# Hot_tub_fill_flow_meter.net
KiCad netlist of a schematic drawn in EAGLE
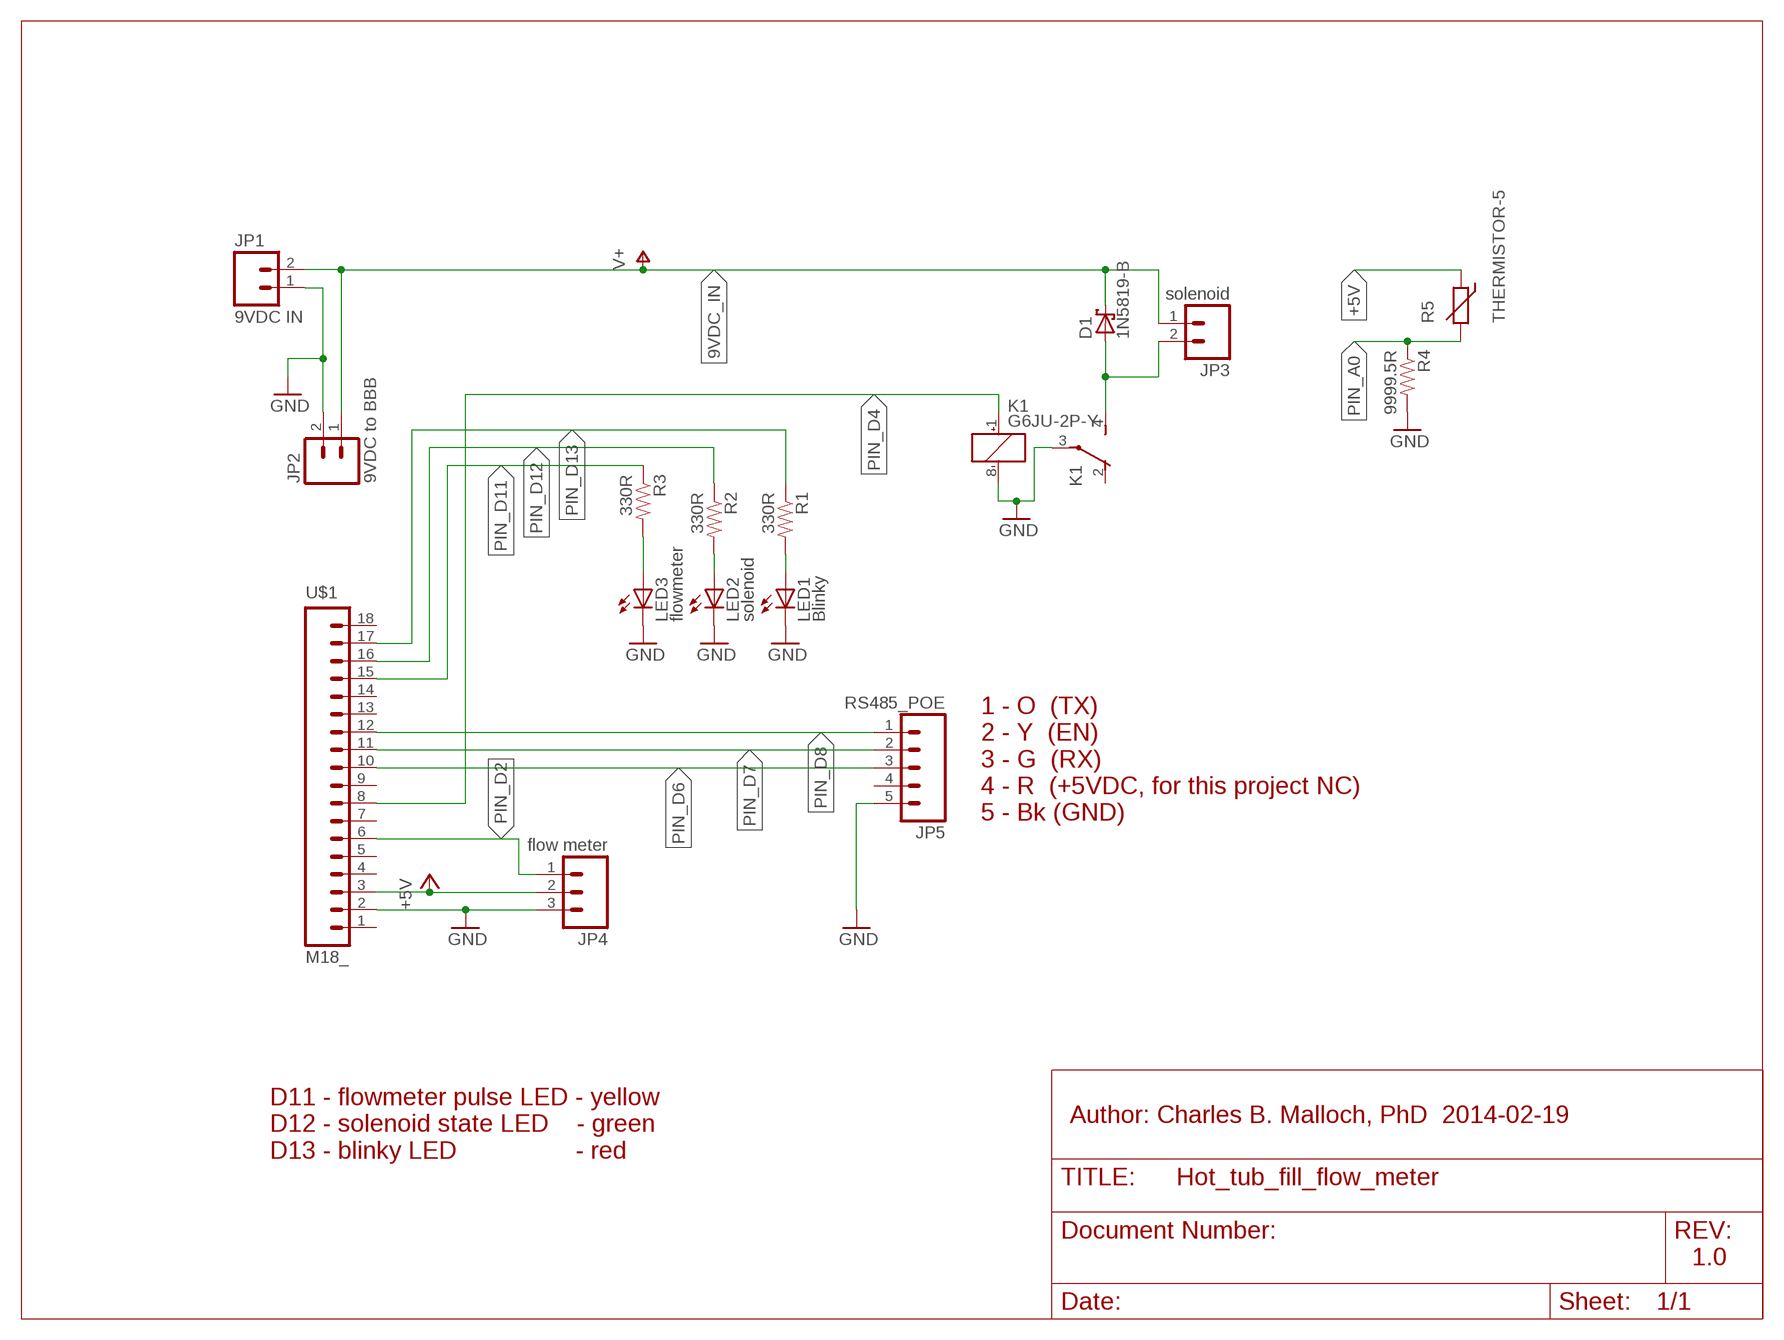
[diagram p0: schematic, sheet 1]

(export (version "E")
  (design (tool "Eeschema 10.0.6"))
  (components
    (comp (ref "D1")
      (value "1N5819-B")
      (footprint "eagle-import:DO41-7.6")
      (libsource (lib "eagle-import") (part "1N5819-B"))
    )
    (comp (ref "JP1")
      (value "9VDC IN")
      (footprint "eagle-import:1X02_LOCK")
      (libsource (lib "eagle-import") (part "M02LOCK"))
    )
    (comp (ref "JP2")
      (value "9VDC to BBB")
      (footprint "eagle-import:1X02_LOCK")
      (libsource (lib "eagle-import") (part "M02LOCK"))
    )
    (comp (ref "JP3")
      (value "solenoid")
      (footprint "eagle-import:1X02_LOCK")
      (libsource (lib "eagle-import") (part "M02LOCK"))
    )
    (comp (ref "JP4")
      (value "flow meter")
      (footprint "eagle-import:1X03_LOCK")
      (libsource (lib "eagle-import") (part "M03LOCK"))
    )
    (comp (ref "JP5")
      (value "RS485_POE")
      (footprint "eagle-import:1X05")
      (libsource (lib "eagle-import") (part "M05PTH"))
    )
    (comp (ref "K1")
      (value "G6JU-2P-Y")
      (footprint "eagle-import:G6J-2P-Y")
      (fields (field (name "MF") "OMRON COMPONENTS USA") (field (name "MPN") "G6JU-2P-Y-DC12"))
      (libsource (lib "eagle-import") (part "G6J-2?-YPU"))
    )
    (comp (ref "LED1")
      (value "Blinky")
      (footprint "eagle-import:LED5MM")
      (libsource (lib "eagle-import") (part "LED5MM"))
    )
    (comp (ref "LED2")
      (value "solenoid")
      (footprint "eagle-import:LED5MM")
      (libsource (lib "eagle-import") (part "LED5MM"))
    )
    (comp (ref "LED3")
      (value "flowmeter")
      (footprint "eagle-import:LED5MM")
      (libsource (lib "eagle-import") (part "LED5MM"))
    )
    (comp (ref "R1")
      (value "330R")
      (footprint "eagle-import:AXIAL-0.3")
      (libsource (lib "eagle-import") (part "RESISTORAXIAL-0.3"))
    )
    (comp (ref "R2")
      (value "330R")
      (footprint "eagle-import:AXIAL-0.3")
      (libsource (lib "eagle-import") (part "RESISTORAXIAL-0.3"))
    )
    (comp (ref "R3")
      (value "330R")
      (footprint "eagle-import:AXIAL-0.3")
      (libsource (lib "eagle-import") (part "RESISTORAXIAL-0.3"))
    )
    (comp (ref "R4")
      (value "9999.5R")
      (footprint "eagle-import:AXIAL-0.3")
      (libsource (lib "eagle-import") (part "RESISTORAXIAL-0.3"))
    )
    (comp (ref "R5")
      (value "THERMISTOR-5")
      (footprint "eagle-import:R-5")
      (libsource (lib "eagle-import") (part "THERMISTOR-5"))
    )
    (comp (ref "U$1")
      (value "M18_")
      (footprint "eagle-import:1X18")
      (libsource (lib "eagle-import") (part "M18_"))
    )
  )
  (nets
    (net (code "1") (name "+5V") (class "Default")
      (node (ref "JP4") (pin "2") (pinfunction "2_2") (pintype "passive"))
      (node (ref "R5") (pin "1") (pinfunction "1_1") (pintype "passive"))
      (node (ref "U$1") (pin "3") (pinfunction "3_3") (pintype "passive"))
    )
    (net (code "2") (name "9VDC_IN") (class "Default")
      (node (ref "D1") (pin "C") (pinfunction "C_C") (pintype "passive"))
      (node (ref "JP1") (pin "2") (pinfunction "2_2") (pintype "passive"))
      (node (ref "JP2") (pin "1") (pinfunction "1_1") (pintype "passive"))
      (node (ref "JP3") (pin "1") (pinfunction "1_1") (pintype "passive"))
    )
    (net (code "3") (name "GND") (class "Default")
      (node (ref "JP1") (pin "1") (pinfunction "1_1") (pintype "passive"))
      (node (ref "JP2") (pin "2") (pinfunction "2_2") (pintype "passive"))
      (node (ref "JP4") (pin "3") (pinfunction "3_3") (pintype "passive"))
      (node (ref "JP5") (pin "5") (pinfunction "5_5") (pintype "passive"))
      (node (ref "K1") (pin "3") (pinfunction "P_3") (pintype "passive"))
      (node (ref "K1") (pin "8") (pinfunction "-_8") (pintype "passive"))
      (node (ref "LED1") (pin "K") (pinfunction "C_K") (pintype "passive"))
      (node (ref "LED2") (pin "K") (pinfunction "C_K") (pintype "passive"))
      (node (ref "LED3") (pin "K") (pinfunction "C_K") (pintype "passive"))
      (node (ref "R4") (pin "P$2") (pinfunction "2_P$2") (pintype "passive"))
      (node (ref "U$1") (pin "2") (pinfunction "2_2") (pintype "passive"))
    )
    (net (code "4") (name "Net-(K1B-S)") (class "Default")
      (node (ref "D1") (pin "A") (pinfunction "A_A") (pintype "passive"))
      (node (ref "JP3") (pin "2") (pinfunction "2_2") (pintype "passive"))
      (node (ref "K1") (pin "4") (pinfunction "S_4") (pintype "passive"))
    )
    (net (code "5") (name "Net-(R1-2)") (class "Default")
      (node (ref "LED1") (pin "A") (pinfunction "A_A") (pintype "passive"))
      (node (ref "R1") (pin "P$2") (pinfunction "2_P$2") (pintype "passive"))
    )
    (net (code "6") (name "Net-(R2-2)") (class "Default")
      (node (ref "LED2") (pin "A") (pinfunction "A_A") (pintype "passive"))
      (node (ref "R2") (pin "P$2") (pinfunction "2_P$2") (pintype "passive"))
    )
    (net (code "7") (name "Net-(R3-2)") (class "Default")
      (node (ref "LED3") (pin "A") (pinfunction "A_A") (pintype "passive"))
      (node (ref "R3") (pin "P$2") (pinfunction "2_P$2") (pintype "passive"))
    )
    (net (code "8") (name "PIN_A0") (class "Default")
      (node (ref "R4") (pin "P$1") (pinfunction "1_P$1") (pintype "passive"))
      (node (ref "R5") (pin "2") (pinfunction "2_2") (pintype "passive"))
    )
    (net (code "9") (name "PIN_D2") (class "Default")
      (node (ref "JP4") (pin "1") (pinfunction "1_1") (pintype "passive"))
      (node (ref "U$1") (pin "6") (pinfunction "6_6") (pintype "passive"))
    )
    (net (code "10") (name "PIN_D4") (class "Default")
      (node (ref "K1") (pin "1") (pinfunction "+_1") (pintype "passive"))
      (node (ref "U$1") (pin "8") (pinfunction "8_8") (pintype "passive"))
    )
    (net (code "11") (name "PIN_D6") (class "Default")
      (node (ref "JP5") (pin "3") (pinfunction "3_3") (pintype "passive"))
      (node (ref "U$1") (pin "10") (pinfunction "10_10") (pintype "passive"))
    )
    (net (code "12") (name "PIN_D7") (class "Default")
      (node (ref "JP5") (pin "2") (pinfunction "2_2") (pintype "passive"))
      (node (ref "U$1") (pin "11") (pinfunction "11_11") (pintype "passive"))
    )
    (net (code "13") (name "PIN_D8") (class "Default")
      (node (ref "JP5") (pin "1") (pinfunction "1_1") (pintype "passive"))
      (node (ref "U$1") (pin "12") (pinfunction "12_12") (pintype "passive"))
    )
    (net (code "14") (name "PIN_D11") (class "Default")
      (node (ref "R3") (pin "P$1") (pinfunction "1_P$1") (pintype "passive"))
      (node (ref "U$1") (pin "15") (pinfunction "15_15") (pintype "passive"))
    )
    (net (code "15") (name "PIN_D12") (class "Default")
      (node (ref "R2") (pin "P$1") (pinfunction "1_P$1") (pintype "passive"))
      (node (ref "U$1") (pin "16") (pinfunction "16_16") (pintype "passive"))
    )
    (net (code "16") (name "PIN_D13") (class "Default")
      (node (ref "R1") (pin "P$1") (pinfunction "1_P$1") (pintype "passive"))
      (node (ref "U$1") (pin "17") (pinfunction "17_17") (pintype "passive"))
    )
    (net (code "17") (name "unconnected-(JP5-Pad4)") (class "Default")
      (node (ref "JP5") (pin "4") (pinfunction "4_4") (pintype "passive"))
    )
    (net (code "18") (name "unconnected-(K1B-O-Pad2)") (class "Default")
      (node (ref "K1") (pin "2") (pinfunction "O_2") (pintype "passive"))
    )
    (net (code "19") (name "unconnected-(U$1-Pad1)") (class "Default")
      (node (ref "U$1") (pin "1") (pinfunction "1_1") (pintype "passive"))
    )
    (net (code "20") (name "unconnected-(U$1-Pad4)") (class "Default")
      (node (ref "U$1") (pin "4") (pinfunction "4_4") (pintype "passive"))
    )
    (net (code "21") (name "unconnected-(U$1-Pad5)") (class "Default")
      (node (ref "U$1") (pin "5") (pinfunction "5_5") (pintype "passive"))
    )
    (net (code "22") (name "unconnected-(U$1-Pad7)") (class "Default")
      (node (ref "U$1") (pin "7") (pinfunction "7_7") (pintype "passive"))
    )
    (net (code "23") (name "unconnected-(U$1-Pad9)") (class "Default")
      (node (ref "U$1") (pin "9") (pinfunction "9_9") (pintype "passive"))
    )
    (net (code "24") (name "unconnected-(U$1-Pad13)") (class "Default")
      (node (ref "U$1") (pin "13") (pinfunction "13_13") (pintype "passive"))
    )
    (net (code "25") (name "unconnected-(U$1-Pad14)") (class "Default")
      (node (ref "U$1") (pin "14") (pinfunction "14_14") (pintype "passive"))
    )
    (net (code "26") (name "unconnected-(U$1-Pad18)") (class "Default")
      (node (ref "U$1") (pin "18") (pinfunction "18_18") (pintype "passive"))
    )
  )
)
